# coreboard.net
KiCad netlist of a schematic drawn in EAGLE
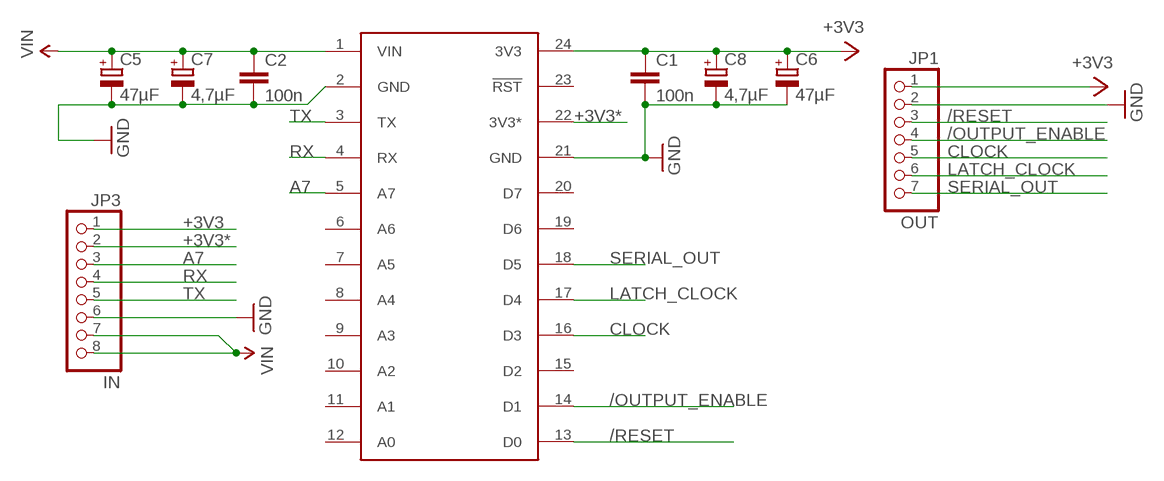
[diagram p0: schematic, sheet 1]

(export (version "E")
  (design (tool "Eeschema 10.0.6"))
  (components
    (comp (ref "C1")
      (value "100n")
      (footprint "eagle-import:C025-024X044")
      (libsource (lib "eagle-import") (part "C-EU025-024X044"))
    )
    (comp (ref "C2")
      (value "100n")
      (footprint "eagle-import:C025-024X044")
      (libsource (lib "eagle-import") (part "C-EU025-024X044"))
    )
    (comp (ref "C5")
      (value "47µF")
      (footprint "eagle-import:E2,5-7")
      (libsource (lib "eagle-import") (part "CPOL-EUE2.5-7"))
    )
    (comp (ref "C6")
      (value "47µF")
      (footprint "eagle-import:E2,5-7")
      (libsource (lib "eagle-import") (part "CPOL-EUE2.5-7"))
    )
    (comp (ref "C7")
      (value "4,7µF")
      (footprint "eagle-import:E2,5-5")
      (libsource (lib "eagle-import") (part "CPOL-EUE2.5-5"))
    )
    (comp (ref "C8")
      (value "4,7µF")
      (footprint "eagle-import:E2,5-5")
      (libsource (lib "eagle-import") (part "CPOL-EUE2.5-5"))
    )
    (comp (ref "JP1")
      (value "OUT")
      (footprint "eagle-import:1X07")
      (libsource (lib "eagle-import") (part "PINHD-1X7"))
    )
    (comp (ref "JP3")
      (value "IN")
      (footprint "eagle-import:1X08")
      (libsource (lib "eagle-import") (part "PINHD-1X8"))
    )
    (comp (ref "U$1")
      (value "SPARK_CORECORE")
      (footprint "eagle-import:SPARK_CORE")
      (libsource (lib "eagle-import") (part "SPARK_CORECORE"))
    )
  )
  (nets
    (net (code "1") (name "+3V3") (class "Default")
      (node (ref "C1") (pin "1") (pinfunction "1_1") (pintype "passive"))
      (node (ref "C6") (pin "+") (pinfunction "+_+") (pintype "passive"))
      (node (ref "C8") (pin "+") (pinfunction "+_+") (pintype "passive"))
      (node (ref "JP1") (pin "1") (pinfunction "1_1") (pintype "passive"))
      (node (ref "JP3") (pin "1") (pinfunction "1_1") (pintype "passive"))
      (node (ref "U$1") (pin "24") (pinfunction "3V3_24") (pintype "power_in"))
    )
    (net (code "2") (name "/+3V3*") (class "Default")
      (node (ref "JP3") (pin "2") (pinfunction "2_2") (pintype "passive"))
      (node (ref "U$1") (pin "22") (pinfunction "3V3*_22") (pintype "power_in"))
    )
    (net (code "3") (name "/A7") (class "Default")
      (node (ref "JP3") (pin "3") (pinfunction "3_3") (pintype "passive"))
      (node (ref "U$1") (pin "5") (pinfunction "A7_5") (pintype "bidirectional"))
    )
    (net (code "4") (name "/CLOCK") (class "Default")
      (node (ref "JP1") (pin "5") (pinfunction "5_5") (pintype "passive"))
      (node (ref "U$1") (pin "16") (pinfunction "D3_16") (pintype "bidirectional"))
    )
    (net (code "5") (name "/LATCH_CLOCK") (class "Default")
      (node (ref "JP1") (pin "6") (pinfunction "6_6") (pintype "passive"))
      (node (ref "U$1") (pin "17") (pinfunction "D4_17") (pintype "bidirectional"))
    )
    (net (code "6") (name "/RX") (class "Default")
      (node (ref "JP3") (pin "4") (pinfunction "4_4") (pintype "passive"))
      (node (ref "U$1") (pin "4") (pinfunction "RX_4") (pintype "bidirectional"))
    )
    (net (code "7") (name "/SERIAL_OUT") (class "Default")
      (node (ref "JP1") (pin "7") (pinfunction "7_7") (pintype "passive"))
      (node (ref "U$1") (pin "18") (pinfunction "D5_18") (pintype "bidirectional"))
    )
    (net (code "8") (name "/TX") (class "Default")
      (node (ref "JP3") (pin "5") (pinfunction "5_5") (pintype "passive"))
      (node (ref "U$1") (pin "3") (pinfunction "TX_3") (pintype "bidirectional"))
    )
    (net (code "9") (name "/{slash}OUTPUT_ENABLE") (class "Default")
      (node (ref "JP1") (pin "4") (pinfunction "4_4") (pintype "passive"))
      (node (ref "U$1") (pin "14") (pinfunction "D1_14") (pintype "bidirectional"))
    )
    (net (code "10") (name "/{slash}RESET") (class "Default")
      (node (ref "JP1") (pin "3") (pinfunction "3_3") (pintype "passive"))
      (node (ref "U$1") (pin "13") (pinfunction "D0_13") (pintype "bidirectional"))
    )
    (net (code "11") (name "GND") (class "Default")
      (node (ref "C1") (pin "2") (pinfunction "2_2") (pintype "passive"))
      (node (ref "C2") (pin "2") (pinfunction "2_2") (pintype "passive"))
      (node (ref "C5") (pin "-") (pinfunction "-_-") (pintype "passive"))
      (node (ref "C6") (pin "-") (pinfunction "-_-") (pintype "passive"))
      (node (ref "C7") (pin "-") (pinfunction "-_-") (pintype "passive"))
      (node (ref "C8") (pin "-") (pinfunction "-_-") (pintype "passive"))
      (node (ref "JP1") (pin "2") (pinfunction "2_2") (pintype "passive"))
      (node (ref "JP3") (pin "6") (pinfunction "6_6") (pintype "passive"))
      (node (ref "U$1") (pin "2") (pinfunction "GND_2") (pintype "power_in"))
      (node (ref "U$1") (pin "21") (pinfunction "GND_21") (pintype "power_in"))
    )
    (net (code "12") (name "VIN") (class "Default")
      (node (ref "C2") (pin "1") (pinfunction "1_1") (pintype "passive"))
      (node (ref "C5") (pin "+") (pinfunction "+_+") (pintype "passive"))
      (node (ref "C7") (pin "+") (pinfunction "+_+") (pintype "passive"))
      (node (ref "JP3") (pin "7") (pinfunction "7_7") (pintype "passive"))
      (node (ref "JP3") (pin "8") (pinfunction "8_8") (pintype "passive"))
      (node (ref "U$1") (pin "1") (pinfunction "VIN_1") (pintype "power_in"))
    )
    (net (code "13") (name "unconnected-(U$1-A0-Pad12)") (class "Default")
      (node (ref "U$1") (pin "12") (pinfunction "A0_12") (pintype "bidirectional"))
    )
    (net (code "14") (name "unconnected-(U$1-A1-Pad11)") (class "Default")
      (node (ref "U$1") (pin "11") (pinfunction "A1_11") (pintype "bidirectional"))
    )
    (net (code "15") (name "unconnected-(U$1-A2-Pad10)") (class "Default")
      (node (ref "U$1") (pin "10") (pinfunction "A2_10") (pintype "bidirectional"))
    )
    (net (code "16") (name "unconnected-(U$1-A3-Pad9)") (class "Default")
      (node (ref "U$1") (pin "9") (pinfunction "A3_9") (pintype "bidirectional"))
    )
    (net (code "17") (name "unconnected-(U$1-A4-Pad8)") (class "Default")
      (node (ref "U$1") (pin "8") (pinfunction "A4_8") (pintype "bidirectional"))
    )
    (net (code "18") (name "unconnected-(U$1-A5-Pad7)") (class "Default")
      (node (ref "U$1") (pin "7") (pinfunction "A5_7") (pintype "bidirectional"))
    )
    (net (code "19") (name "unconnected-(U$1-A6-Pad6)") (class "Default")
      (node (ref "U$1") (pin "6") (pinfunction "A6_6") (pintype "bidirectional"))
    )
    (net (code "20") (name "unconnected-(U$1-D2-Pad15)") (class "Default")
      (node (ref "U$1") (pin "15") (pinfunction "D2_15") (pintype "bidirectional"))
    )
    (net (code "21") (name "unconnected-(U$1-D6-Pad19)") (class "Default")
      (node (ref "U$1") (pin "19") (pinfunction "D6_19") (pintype "bidirectional"))
    )
    (net (code "22") (name "unconnected-(U$1-D7-Pad20)") (class "Default")
      (node (ref "U$1") (pin "20") (pinfunction "D7_20") (pintype "bidirectional"))
    )
    (net (code "23") (name "unconnected-(U$1-~{RST}-Pad23)") (class "Default")
      (node (ref "U$1") (pin "23") (pinfunction "~{RST}_23") (pintype "bidirectional"))
    )
  )
)
